# MultiVibrator.net
KiCad netlist of a schematic drawn in Altium Designer
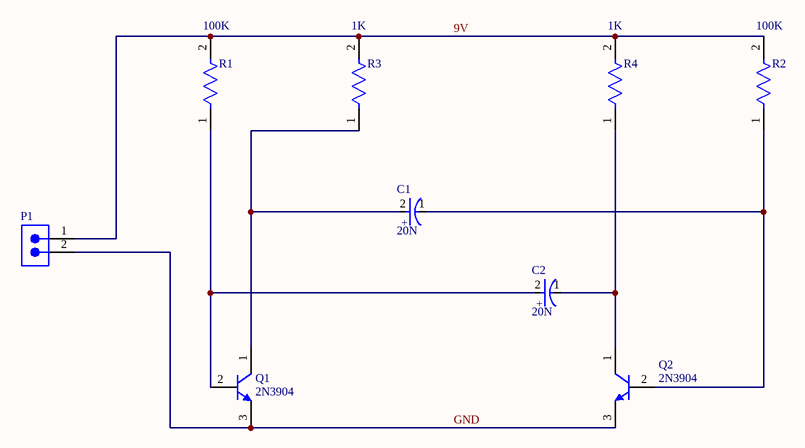
[diagram p0: MultiVibrator.SchDoc]

(export (version "E")
  (design (tool "Eeschema 10.0.6"))
  (components
    (comp (ref "C1")
      (value "~")
      (footprint "FP-600D107G070DL4-MFG")
      (description "600D107G070DL4 Cap Alum 100UF 70V Axial")
      (fields (field (name "CAPACITANCE") "20N"))
      (libsource (lib "Altium Content Vault") (part "a00bbbee19879c290e62620ae7e47b1"))
    )
    (comp (ref "C2")
      (value "~")
      (footprint "FP-600D107G070DL4-MFG")
      (description "600D107G070DL4 Cap Alum 100UF 70V Axial")
      (fields (field (name "CAPACITANCE") "20N"))
      (libsource (lib "Altium Content Vault") (part "a00bbbee19879c290e62620ae7e47b1"))
    )
    (comp (ref "P1")
      (value "61900211121")
      (footprint "61900211121")
      (libsource (lib "Altium Content Vault") (part "Header_Male_1R_02P"))
    )
    (comp (ref "Q1")
      (value "2N3904")
      (footprint "ONSC-TO-92-3-29-11")
      (description "Amplifier Transistor, NPN Silicon, 3-Pin TO-92, Bulk Box")
      (fields (field (name "PARTNUMBER") "BC337") (field (name "MANUFACTURER") "On Semiconductor"))
      (libsource (lib "Altium Content Vault") (part "ONSC-NPN-C1B2E3-3"))
    )
    (comp (ref "Q2")
      (value "2N3904")
      (footprint "ONSC-TO-92-3-29-11")
      (description "Amplifier Transistor, NPN Silicon, 3-Pin TO-92, Bulk Box")
      (fields (field (name "PARTNUMBER") "BC337") (field (name "MANUFACTURER") "On Semiconductor"))
      (libsource (lib "Altium Content Vault") (part "ONSC-NPN-C1B2E3-3"))
    )
    (comp (ref "R1")
      (value "~")
      (footprint "FP-MRS25-MFG")
      (description "RES 562 OHM 0.6W 1% AXIAL")
      (fields (field (name "TOLERANCE") "1%") (field (name "RESISTANCE") "100K"))
      (libsource (lib "Altium Content Vault") (part "1029c3af85768c4190bb7ad29bc67b5"))
    )
    (comp (ref "R2")
      (value "~")
      (footprint "FP-MRS25-MFG")
      (description "RES 562 OHM 0.6W 1% AXIAL")
      (fields (field (name "TOLERANCE") "1%") (field (name "RESISTANCE") "100K"))
      (libsource (lib "Altium Content Vault") (part "1029c3af85768c4190bb7ad29bc67b5"))
    )
    (comp (ref "R3")
      (value "~")
      (footprint "FP-MRS25-MFG")
      (description "RES 562 OHM 0.6W 1% AXIAL")
      (fields (field (name "TOLERANCE") "1%") (field (name "RESISTANCE") "1K"))
      (libsource (lib "Altium Content Vault") (part "1029c3af85768c4190bb7ad29bc67b5"))
    )
    (comp (ref "R4")
      (value "~")
      (footprint "FP-MRS25-MFG")
      (description "RES 562 OHM 0.6W 1% AXIAL")
      (fields (field (name "TOLERANCE") "1%") (field (name "RESISTANCE") "1K"))
      (libsource (lib "Altium Content Vault") (part "1029c3af85768c4190bb7ad29bc67b5"))
    )
  )
  (nets
    (net (code "1") (name "/9V") (class "Default")
      (node (ref "P1") (pin "1") (pinfunction "1_1") (pintype "passive"))
      (node (ref "R1") (pin "2") (pinfunction "2_2") (pintype "passive"))
      (node (ref "R2") (pin "2") (pinfunction "2_2") (pintype "passive"))
      (node (ref "R3") (pin "2") (pinfunction "2_2") (pintype "passive"))
      (node (ref "R4") (pin "2") (pinfunction "2_2") (pintype "passive"))
    )
    (net (code "2") (name "/GND") (class "Default")
      (node (ref "P1") (pin "2") (pinfunction "2_2") (pintype "passive"))
      (node (ref "Q1") (pin "3") (pinfunction "E_3") (pintype "passive"))
      (node (ref "Q2") (pin "3") (pinfunction "E_3") (pintype "passive"))
    )
    (net (code "3") (name "Net-(C1-A)") (class "Default")
      (node (ref "C1") (pin "2") (pinfunction "A_2") (pintype "passive"))
      (node (ref "Q1") (pin "1") (pinfunction "C_1") (pintype "passive"))
      (node (ref "R3") (pin "1") (pinfunction "1_1") (pintype "passive"))
    )
    (net (code "4") (name "Net-(C1-C)") (class "Default")
      (node (ref "C1") (pin "1") (pinfunction "C_1") (pintype "passive"))
      (node (ref "Q2") (pin "2") (pinfunction "B_2") (pintype "passive"))
      (node (ref "R2") (pin "1") (pinfunction "1_1") (pintype "passive"))
    )
    (net (code "5") (name "Net-(C2-A)") (class "Default")
      (node (ref "C2") (pin "2") (pinfunction "A_2") (pintype "passive"))
      (node (ref "Q1") (pin "2") (pinfunction "B_2") (pintype "passive"))
      (node (ref "R1") (pin "1") (pinfunction "1_1") (pintype "passive"))
    )
    (net (code "6") (name "Net-(C2-C)") (class "Default")
      (node (ref "C2") (pin "1") (pinfunction "C_1") (pintype "passive"))
      (node (ref "Q2") (pin "1") (pinfunction "C_1") (pintype "passive"))
      (node (ref "R4") (pin "1") (pinfunction "1_1") (pintype "passive"))
    )
  )
)
